# eval.net
KiCad netlist of a schematic drawn in Altium Designer
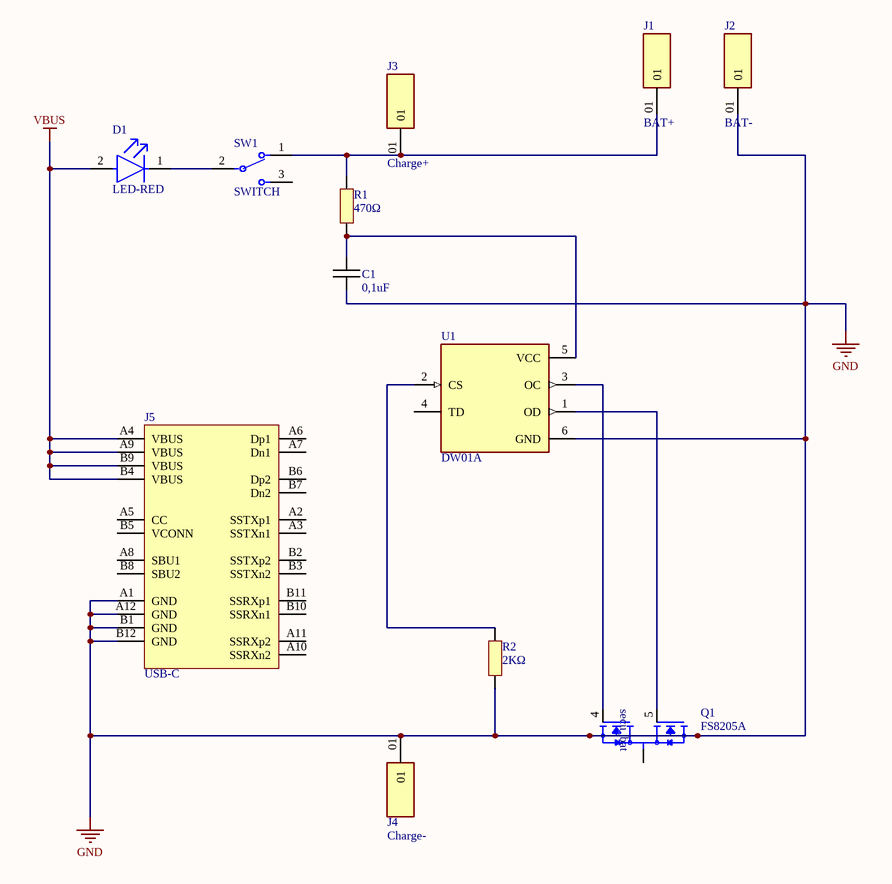
[diagram p0: eval.SchDoc]

(export (version "E")
  (design (tool "Eeschema 10.0.6"))
  (components
    (comp (ref "C1")
      (value "0,1uF")
      (footprint "SMD-1005-CAP")
      (libsource (lib "Schematic_lib") (part "CAPACITOR"))
    )
    (comp (ref "D1")
      (value "LED-RED")
      (footprint "SMD-1608-LED")
      (description "LED GREEN CLEAR CHIP SMD LTST-C190GKT")
      (fields (field (name "VOLTAGE") "2V"))
      (libsource (lib "Schematic_lib") (part "LED-RED"))
    )
    (comp (ref "J1")
      (value "BAT+")
      (footprint "HEADER")
      (description "Connector Header Through Hole 1 position")
      (fields (field (name "MF") "Samtec") (field (name "MP") "MTMM-101-05-G-S-225"))
      (libsource (lib "") (part "HEADER_1"))
    )
    (comp (ref "J2")
      (value "BAT-")
      (footprint "HEADER")
      (description "Connector Header Through Hole 1 position")
      (fields (field (name "MF") "Samtec") (field (name "MP") "MTMM-101-05-G-S-225"))
      (libsource (lib "") (part "HEADER_1"))
    )
    (comp (ref "J3")
      (value "Charge+")
      (footprint "HEADER")
      (description "Connector Header Through Hole 1 position")
      (fields (field (name "MF") "Samtec") (field (name "MP") "MTMM-101-05-G-S-225"))
      (libsource (lib "") (part "HEADER_1"))
    )
    (comp (ref "J4")
      (value "Charge-")
      (footprint "HEADER")
      (description "Connector Header Through Hole 1 position")
      (fields (field (name "MF") "Samtec") (field (name "MP") "MTMM-101-05-G-S-225"))
      (libsource (lib "Schematic_lib") (part "HEADER"))
    )
    (comp (ref "J5") (value "USB-C") (footprint "USB-C") (libsource (lib "Schematic_lib") (part "USB-C")))
    (comp (ref "Q1")
      (value "FS8205A")
      (footprint "FS8205A")
      (fields (field (name "MF") "Fortune Semiconductor"))
      (libsource (lib "Schematic_lib") (part "FS8205A"))
    )
    (comp (ref "R1")
      (value "470Ω")
      (footprint "SMD-1005-RES")
      (libsource (lib "Schematic_lib") (part "RESISTOR"))
    )
    (comp (ref "R2") (value "2KΩ") (footprint "SMD-1005-RES") (libsource (lib "") (part "RESISTOR_1")))
    (comp (ref "SW1")
      (value "SWITCH")
      (footprint "SMD-SWITCH")
      (description "SWITCH SLIDE SPDT 300MA 6V JS102011SCQN")
      (libsource (lib "Schematic_lib") (part "SWITCH"))
    )
    (comp (ref "U1")
      (value "DW01A")
      (footprint "DW01A")
      (description "One Cell Lithium-ion/Polymer Battery Protection IC")
      (fields (field (name "MF") "Fortune Semiconductor"))
      (libsource (lib "Schematic_lib") (part "DW01A"))
    )
  )
  (nets
    (net (code "1") (name "GND") (class "Default")
      (node (ref "C1") (pin "2") (pinfunction "2_2") (pintype "passive"))
      (node (ref "J2") (pin "01") (pinfunction "01_01") (pintype "passive"))
      (node (ref "J4") (pin "01") (pinfunction "01_01") (pintype "passive"))
      (node (ref "J5") (pin "A1") (pinfunction "GND_A1") (pintype "passive"))
      (node (ref "J5") (pin "A12") (pinfunction "GND_A12") (pintype "passive"))
      (node (ref "J5") (pin "B1") (pinfunction "GND_B1") (pintype "passive"))
      (node (ref "J5") (pin "B12") (pinfunction "GND_B12") (pintype "passive"))
      (node (ref "Q1") (pin "2") (pinfunction "S1_2") (pintype "passive"))
      (node (ref "Q1") (pin "3") (pinfunction "S1_3") (pintype "passive"))
      (node (ref "Q1") (pin "6") (pinfunction "S2_6") (pintype "passive"))
      (node (ref "Q1") (pin "7") (pinfunction "S2_7") (pintype "passive"))
      (node (ref "R2") (pin "2") (pinfunction "2_2") (pintype "passive"))
      (node (ref "U1") (pin "6") (pinfunction "GND_6") (pintype "power_in"))
    )
    (net (code "2") (name "Net-(D1-C)") (class "Default")
      (node (ref "D1") (pin "1") (pinfunction "C_1") (pintype "passive"))
      (node (ref "SW1") (pin "2") (pinfunction "C_2") (pintype "passive"))
    )
    (net (code "3") (name "Net-(J1-Pad01)") (class "Default")
      (node (ref "J1") (pin "01") (pinfunction "01_01") (pintype "passive"))
      (node (ref "J3") (pin "01") (pinfunction "01_01") (pintype "passive"))
      (node (ref "R1") (pin "2") (pinfunction "2_2") (pintype "passive"))
      (node (ref "SW1") (pin "1") (pinfunction "1_1") (pintype "passive"))
    )
    (net (code "4") (name "Net-(Q1-D12-Pad1)") (class "Default")
      (node (ref "Q1") (pin "1") (pinfunction "D12_1") (pintype "passive"))
      (node (ref "Q1") (pin "8") (pinfunction "D12_8") (pintype "passive"))
    )
    (net (code "5") (name "Net-(Q1-G1)") (class "Default")
      (node (ref "Q1") (pin "4") (pinfunction "G1_4") (pintype "passive"))
      (node (ref "U1") (pin "3") (pinfunction "OC_3") (pintype "output"))
    )
    (net (code "6") (name "Net-(Q1-G2)") (class "Default")
      (node (ref "Q1") (pin "5") (pinfunction "G2_5") (pintype "passive"))
      (node (ref "U1") (pin "1") (pinfunction "OD_1") (pintype "output"))
    )
    (net (code "7") (name "Net-(U1-CS)") (class "Default")
      (node (ref "R2") (pin "1") (pinfunction "1_1") (pintype "passive"))
      (node (ref "U1") (pin "2") (pinfunction "CS_2") (pintype "input"))
    )
    (net (code "8") (name "Net-(U1-VCC)") (class "Default")
      (node (ref "C1") (pin "1") (pinfunction "1_1") (pintype "passive"))
      (node (ref "R1") (pin "1") (pinfunction "1_1") (pintype "passive"))
      (node (ref "U1") (pin "5") (pinfunction "VCC_5") (pintype "power_in"))
    )
    (net (code "9") (name "VBUS") (class "Default")
      (node (ref "D1") (pin "2") (pinfunction "A_2") (pintype "passive"))
      (node (ref "J5") (pin "A4") (pinfunction "VBUS_A4") (pintype "passive"))
      (node (ref "J5") (pin "A9") (pinfunction "VBUS_A9") (pintype "passive"))
      (node (ref "J5") (pin "B4") (pinfunction "VBUS_B4") (pintype "passive"))
      (node (ref "J5") (pin "B9") (pinfunction "VBUS_B9") (pintype "passive"))
    )
    (net (code "10") (name "unconnected-(J5-CC-PadA5)") (class "Default")
      (node (ref "J5") (pin "A5") (pinfunction "CC_A5") (pintype "passive"))
    )
    (net (code "11") (name "unconnected-(J5-Dn1-PadA7)") (class "Default")
      (node (ref "J5") (pin "A7") (pinfunction "Dn1_A7") (pintype "passive"))
    )
    (net (code "12") (name "unconnected-(J5-Dn2-PadB7)") (class "Default")
      (node (ref "J5") (pin "B7") (pinfunction "Dn2_B7") (pintype "passive"))
    )
    (net (code "13") (name "unconnected-(J5-Dp1-PadA6)") (class "Default")
      (node (ref "J5") (pin "A6") (pinfunction "Dp1_A6") (pintype "passive"))
    )
    (net (code "14") (name "unconnected-(J5-Dp2-PadB6)") (class "Default")
      (node (ref "J5") (pin "B6") (pinfunction "Dp2_B6") (pintype "passive"))
    )
    (net (code "15") (name "unconnected-(J5-SBU1-PadA8)") (class "Default")
      (node (ref "J5") (pin "A8") (pinfunction "SBU1_A8") (pintype "passive"))
    )
    (net (code "16") (name "unconnected-(J5-SBU2-PadB8)") (class "Default")
      (node (ref "J5") (pin "B8") (pinfunction "SBU2_B8") (pintype "passive"))
    )
    (net (code "17") (name "unconnected-(J5-SSRXn1-PadB10)") (class "Default")
      (node (ref "J5") (pin "B10") (pinfunction "SSRXn1_B10") (pintype "passive"))
    )
    (net (code "18") (name "unconnected-(J5-SSRXn2-PadA10)") (class "Default")
      (node (ref "J5") (pin "A10") (pinfunction "SSRXn2_A10") (pintype "passive"))
    )
    (net (code "19") (name "unconnected-(J5-SSRXp1-PadB11)") (class "Default")
      (node (ref "J5") (pin "B11") (pinfunction "SSRXp1_B11") (pintype "passive"))
    )
    (net (code "20") (name "unconnected-(J5-SSRXp2-PadA11)") (class "Default")
      (node (ref "J5") (pin "A11") (pinfunction "SSRXp2_A11") (pintype "passive"))
    )
    (net (code "21") (name "unconnected-(J5-SSTXn1-PadA3)") (class "Default")
      (node (ref "J5") (pin "A3") (pinfunction "SSTXn1_A3") (pintype "passive"))
    )
    (net (code "22") (name "unconnected-(J5-SSTXn2-PadB3)") (class "Default")
      (node (ref "J5") (pin "B3") (pinfunction "SSTXn2_B3") (pintype "passive"))
    )
    (net (code "23") (name "unconnected-(J5-SSTXp1-PadA2)") (class "Default")
      (node (ref "J5") (pin "A2") (pinfunction "SSTXp1_A2") (pintype "passive"))
    )
    (net (code "24") (name "unconnected-(J5-SSTXp2-PadB2)") (class "Default")
      (node (ref "J5") (pin "B2") (pinfunction "SSTXp2_B2") (pintype "passive"))
    )
    (net (code "25") (name "unconnected-(J5-VCONN-PadB5)") (class "Default")
      (node (ref "J5") (pin "B5") (pinfunction "VCONN_B5") (pintype "passive"))
    )
    (net (code "26") (name "unconnected-(SW1-Pad3)") (class "Default")
      (node (ref "SW1") (pin "3") (pinfunction "3_3") (pintype "passive"))
    )
    (net (code "27") (name "unconnected-(U1-TD-Pad4)") (class "Default")
      (node (ref "U1") (pin "4") (pinfunction "TD_4") (pintype "passive"))
    )
  )
)
